# attiny_micro.net
KiCad netlist of a schematic drawn in EAGLE
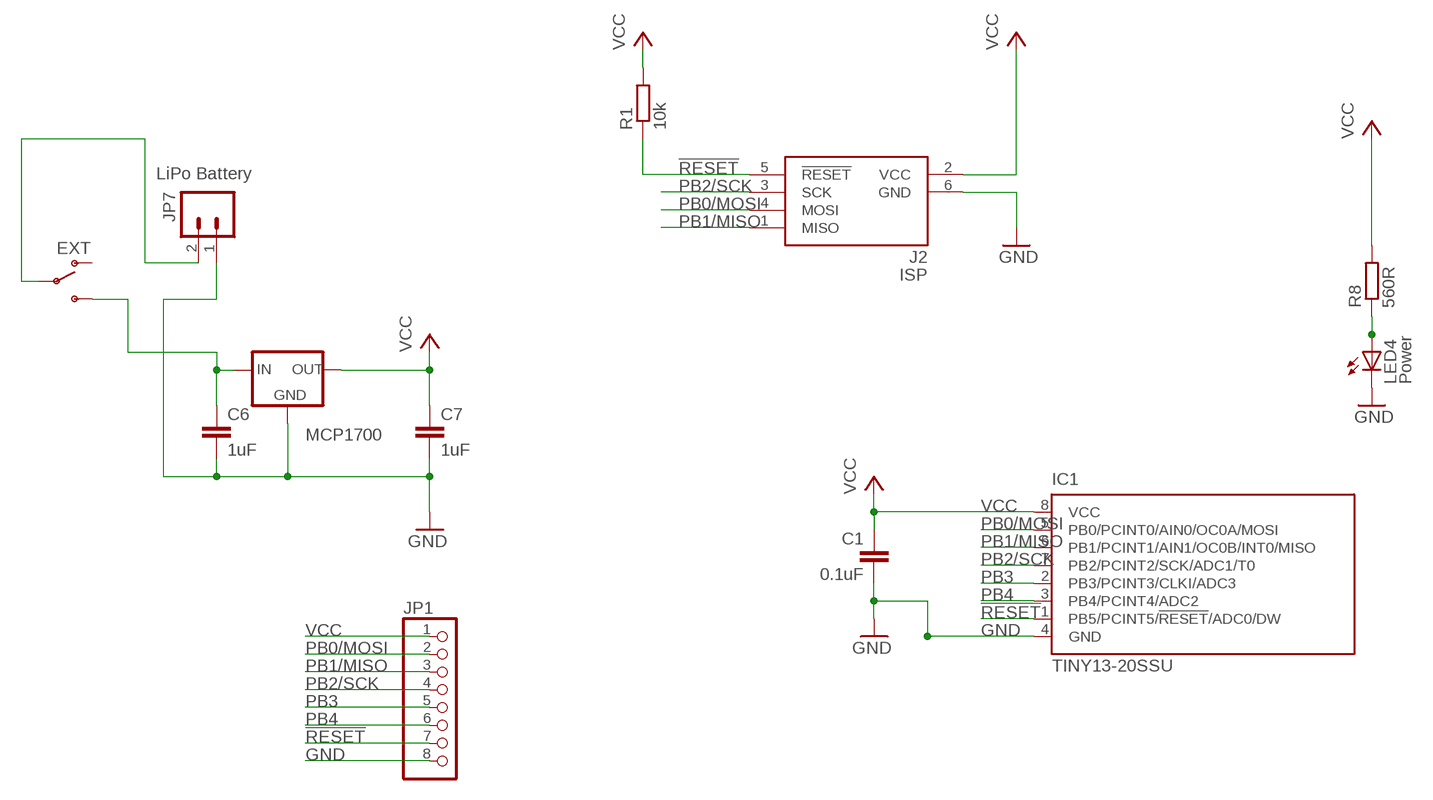
[diagram p0: schematic, sheet 1]

(export (version "E")
  (design (tool "Eeschema 10.0.6"))
  (components
    (comp (ref "C1")
      (value "0.1uF")
      (footprint "eagle-import:C0805")
      (libsource (lib "eagle-import") (part "C-EUC0805"))
    )
    (comp (ref "C6")
      (value "1uF")
      (footprint "eagle-import:C0805")
      (libsource (lib "eagle-import") (part "C-EUC0805"))
    )
    (comp (ref "C7")
      (value "1uF")
      (footprint "eagle-import:C0805")
      (libsource (lib "eagle-import") (part "C-EUC0805"))
    )
    (comp (ref "IC1")
      (value "TINY13-20SSU")
      (footprint "eagle-import:8S1")
      (fields (field (name "MPN") "ATTINY13-20SSU"))
      (libsource (lib "eagle-import") (part "TINY13SSU-20"))
    )
    (comp (ref "J2")
      (value "ISP")
      (footprint "eagle-import:CON6P2R")
      (libsource (lib "eagle-import") (part "AVRISP6"))
    )
    (comp (ref "JP1")
      (value "PINHD-1X8")
      (footprint "eagle-import:1X08")
      (libsource (lib "eagle-import") (part "PINHD-1X8"))
    )
    (comp (ref "JP7")
      (value "LiPo Battery")
      (footprint "eagle-import:JST-2-PTH")
      (libsource (lib "eagle-import") (part "M02JST-PTH-2"))
    )
    (comp (ref "LED4")
      (value "Power")
      (footprint "eagle-import:CHIP-LED0805")
      (libsource (lib "eagle-import") (part "LEDCHIP-LED0805"))
    )
    (comp (ref "MCP1700")
      (value "MCP1700")
      (footprint "eagle-import:SOT-23")
      (libsource (lib "eagle-import") (part "MCP1700SOT-23"))
    )
    (comp (ref "ON")
      (value "EXT")
      (footprint "eagle-import:SWITCH-SPDT")
      (libsource (lib "eagle-import") (part "SWITCH-SPSTPTH"))
    )
    (comp (ref "R1")
      (value "10k")
      (footprint "eagle-import:R0805")
      (libsource (lib "eagle-import") (part "R-EU_R0805"))
    )
    (comp (ref "R8")
      (value "560R")
      (footprint "eagle-import:R0805")
      (libsource (lib "eagle-import") (part "R-EU_R0805"))
    )
  )
  (nets
    (net (code "1") (name "/PB0{slash}MOSI") (class "Default")
      (node (ref "IC1") (pin "5") (pinfunction "PB0/PCINT0/AIN0/OC0A/MOSI_5") (pintype "bidirectional"))
      (node (ref "J2") (pin "4") (pinfunction "MOSI_4") (pintype "output"))
      (node (ref "JP1") (pin "2") (pinfunction "2_2") (pintype "passive"))
    )
    (net (code "2") (name "/PB1{slash}MISO") (class "Default")
      (node (ref "IC1") (pin "6") (pinfunction "PB1/PCINT1/AIN1/OC0B/INT0/MISO_6") (pintype "bidirectional"))
      (node (ref "J2") (pin "1") (pinfunction "MISO_1") (pintype "input"))
      (node (ref "JP1") (pin "3") (pinfunction "3_3") (pintype "passive"))
    )
    (net (code "3") (name "/PB2{slash}SCK") (class "Default")
      (node (ref "IC1") (pin "7") (pinfunction "PB2/PCINT2/SCK/ADC1/T0_7") (pintype "bidirectional"))
      (node (ref "J2") (pin "3") (pinfunction "SCK_3") (pintype "output"))
      (node (ref "JP1") (pin "4") (pinfunction "4_4") (pintype "passive"))
    )
    (net (code "4") (name "/PB3") (class "Default")
      (node (ref "IC1") (pin "2") (pinfunction "PB3/PCINT3/CLKI/ADC3_2") (pintype "bidirectional"))
      (node (ref "JP1") (pin "5") (pinfunction "5_5") (pintype "passive"))
    )
    (net (code "5") (name "/PB4") (class "Default")
      (node (ref "IC1") (pin "3") (pinfunction "PB4/PCINT4/ADC2_3") (pintype "bidirectional"))
      (node (ref "JP1") (pin "6") (pinfunction "6_6") (pintype "passive"))
    )
    (net (code "6") (name "/~{RESET}") (class "Default")
      (node (ref "IC1") (pin "1") (pinfunction "PB5/PCINT5/~{RESET}/ADC0/DW_1") (pintype "bidirectional"))
      (node (ref "J2") (pin "5") (pinfunction "~{RESET}_5") (pintype "output"))
      (node (ref "JP1") (pin "7") (pinfunction "7_7") (pintype "passive"))
      (node (ref "R1") (pin "1") (pinfunction "1_1") (pintype "passive"))
    )
    (net (code "7") (name "GND") (class "Default")
      (node (ref "C1") (pin "2") (pinfunction "2_2") (pintype "passive"))
      (node (ref "C6") (pin "2") (pinfunction "2_2") (pintype "passive"))
      (node (ref "C7") (pin "2") (pinfunction "2_2") (pintype "passive"))
      (node (ref "IC1") (pin "4") (pinfunction "GND_4") (pintype "power_in"))
      (node (ref "J2") (pin "6") (pinfunction "GND_6") (pintype "power_in"))
      (node (ref "JP1") (pin "8") (pinfunction "8_8") (pintype "passive"))
      (node (ref "JP7") (pin "1") (pinfunction "1_1") (pintype "passive"))
      (node (ref "LED4") (pin "C") (pinfunction "C_C") (pintype "passive"))
      (node (ref "MCP1700") (pin "1") (pinfunction "GND_1") (pintype "input"))
    )
    (net (code "8") (name "Net-(LED4-PadA)") (class "Default")
      (node (ref "LED4") (pin "A") (pinfunction "A_A") (pintype "passive"))
      (node (ref "R8") (pin "1") (pinfunction "1_1") (pintype "passive"))
    )
    (net (code "9") (name "Net-(MCP1700-IN)") (class "Default")
      (node (ref "C6") (pin "1") (pinfunction "1_1") (pintype "passive"))
      (node (ref "MCP1700") (pin "3") (pinfunction "IN_3") (pintype "input"))
      (node (ref "ON") (pin "3") (pinfunction "S_3") (pintype "passive"))
    )
    (net (code "10") (name "Net-(ON-P)") (class "Default")
      (node (ref "JP7") (pin "2") (pinfunction "2_2") (pintype "passive"))
      (node (ref "ON") (pin "2") (pinfunction "P_2") (pintype "passive"))
    )
    (net (code "11") (name "VCC") (class "Default")
      (node (ref "C1") (pin "1") (pinfunction "1_1") (pintype "passive"))
      (node (ref "C7") (pin "1") (pinfunction "1_1") (pintype "passive"))
      (node (ref "IC1") (pin "8") (pinfunction "VCC_8") (pintype "power_in"))
      (node (ref "J2") (pin "2") (pinfunction "VCC_2") (pintype "power_in"))
      (node (ref "JP1") (pin "1") (pinfunction "1_1") (pintype "passive"))
      (node (ref "MCP1700") (pin "2") (pinfunction "OUT_2") (pintype "passive"))
      (node (ref "R1") (pin "2") (pinfunction "2_2") (pintype "passive"))
      (node (ref "R8") (pin "2") (pinfunction "2_2") (pintype "passive"))
    )
    (net (code "12") (name "unconnected-(ON-O-Pad1)") (class "Default")
      (node (ref "ON") (pin "1") (pinfunction "O_1") (pintype "passive"))
    )
  )
)
